# TJMakes_Relay.net
KiCad netlist of a schematic drawn in EasyEDA Pro
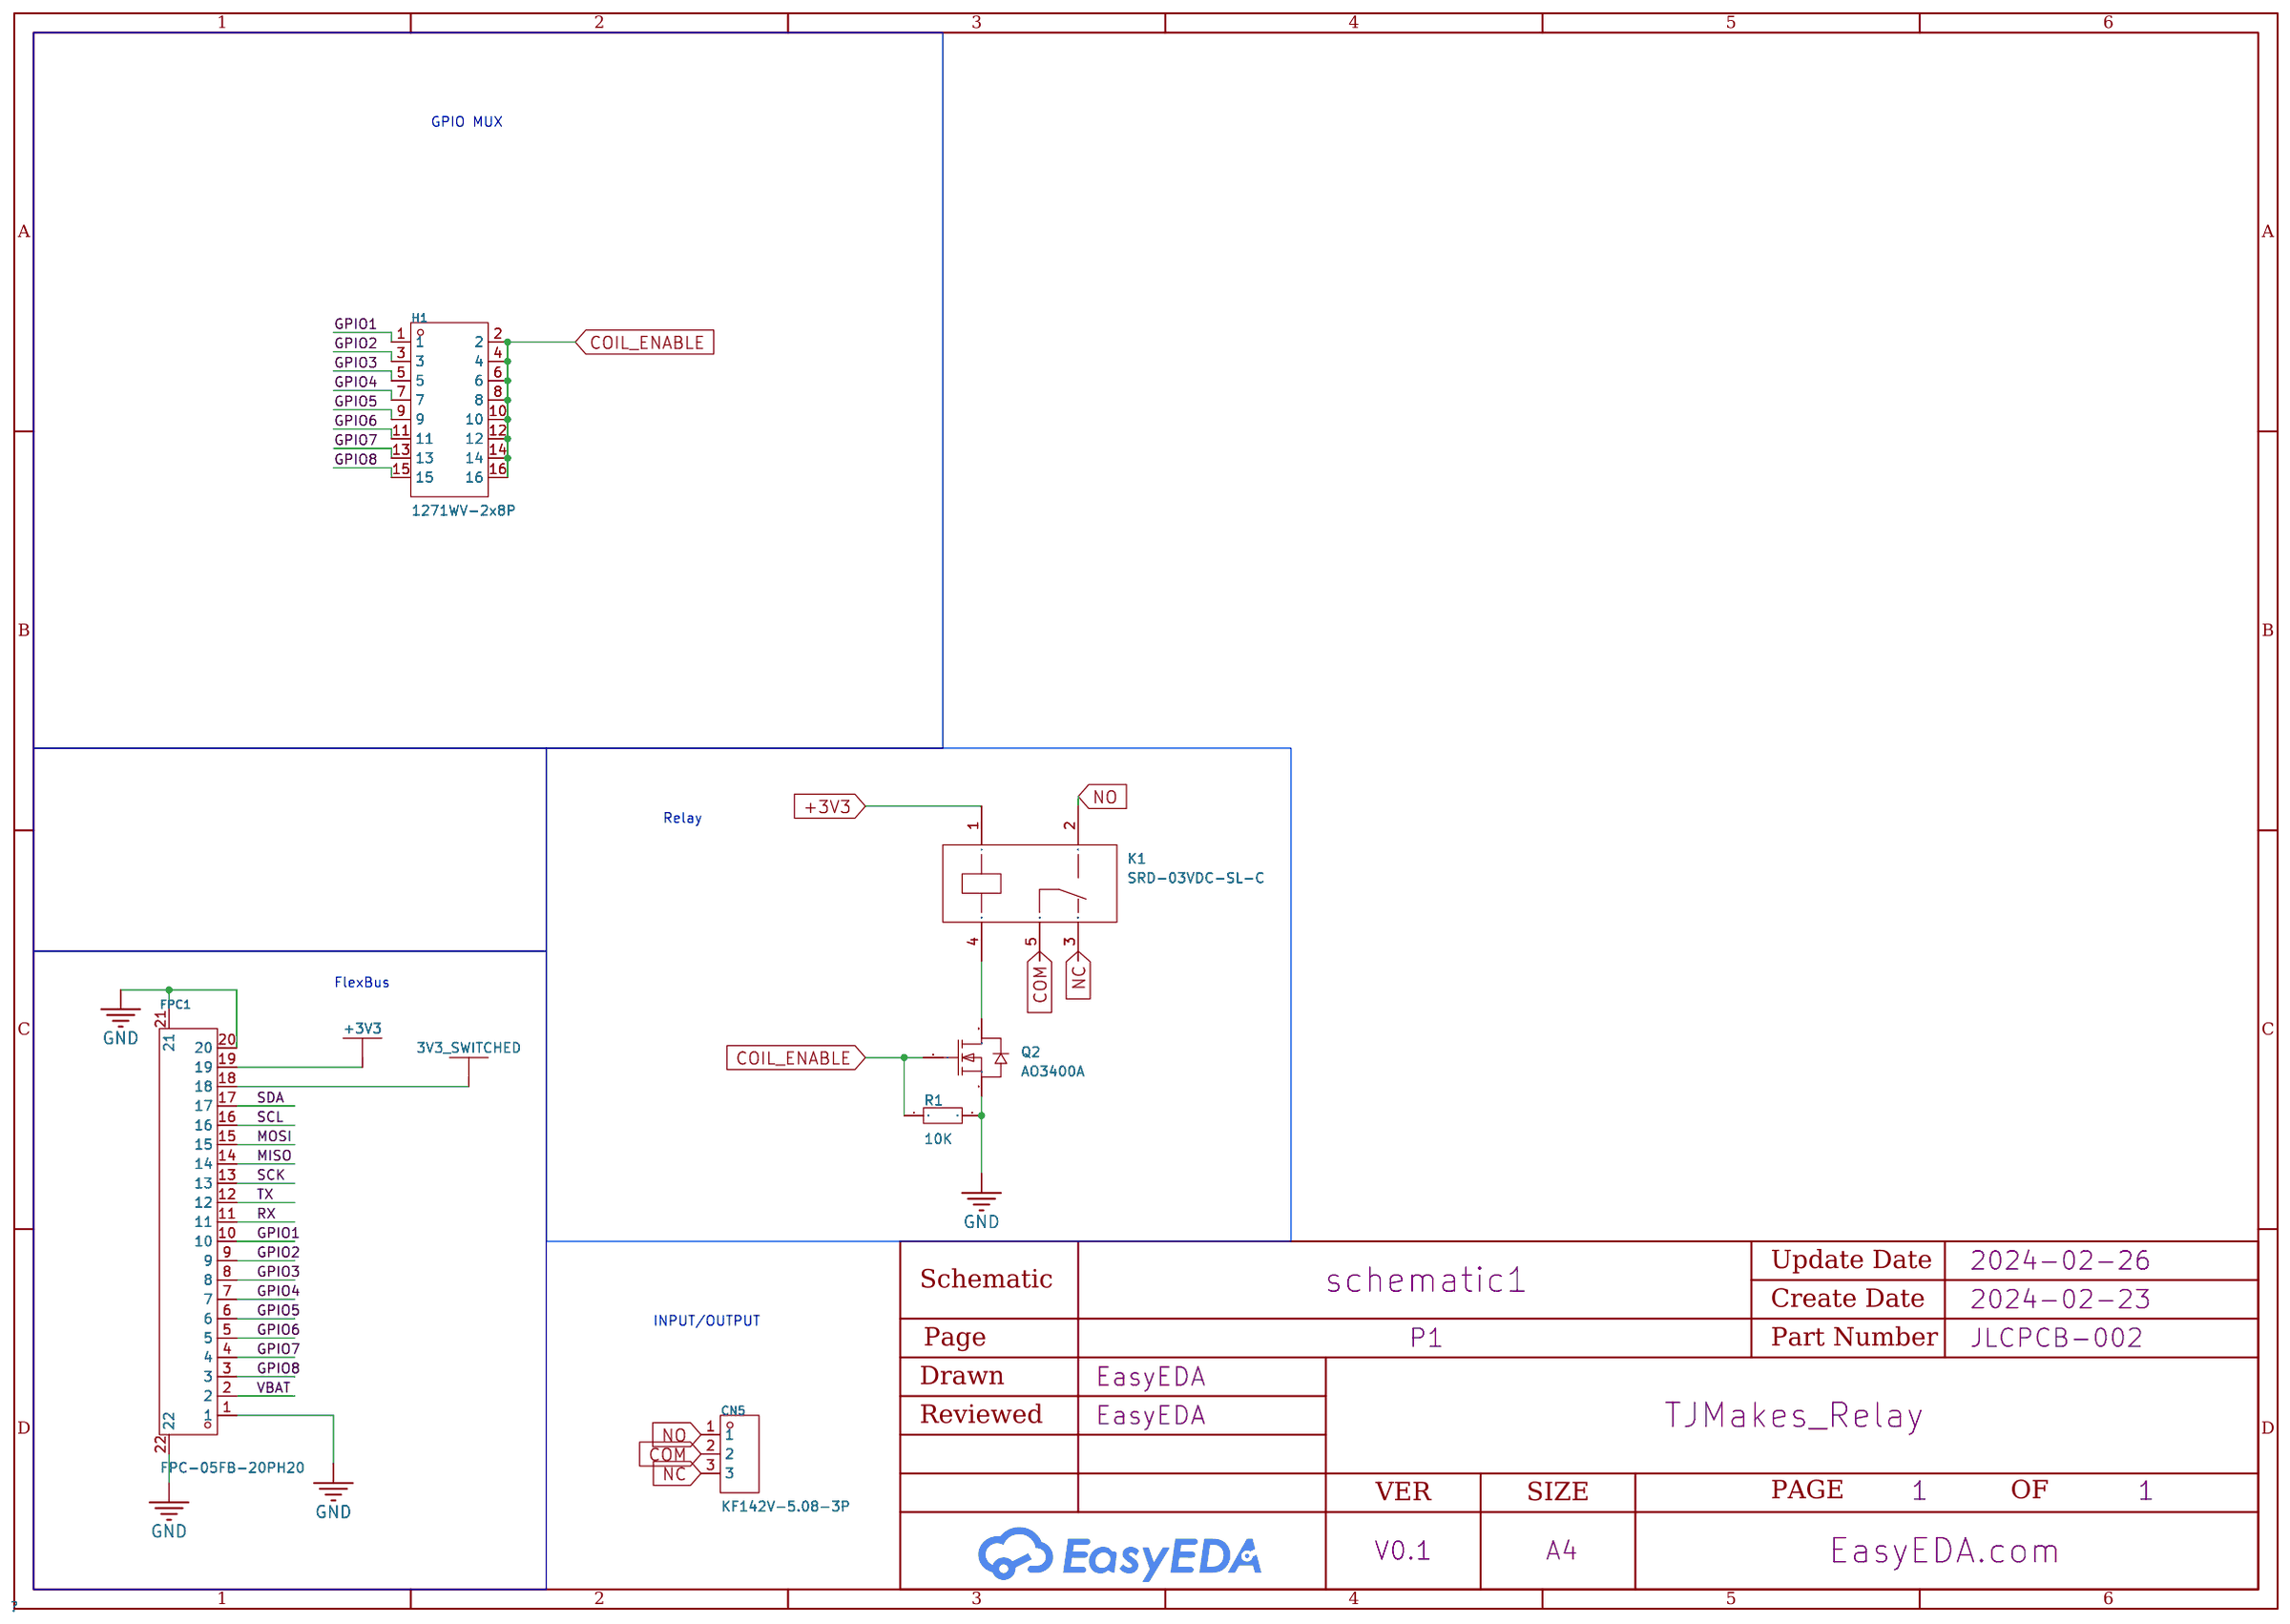
[diagram p0: schematic sheet]

(export (version "E")
  (design (tool "Eeschema 10.0.6"))
  (components
    (comp (ref "CN5")
      (value "KF142V-5.08-3P")
      (footprint "easyedapro:CONN-TH_3P-P5.08_KF142V-5.08-3P")
      (fields (field (name "Manufacturer") "KEFA(科发)"))
      (libsource (lib "easyedapro") (part "KF142V-5.08-3P"))
    )
    (comp (ref "FPC1")
      (value "FPC-05FB-20PH20")
      (footprint "easyedapro:FPC-SMD_20P-P0.50_FPC-05FB-20PH20")
      (fields (field (name "Manufacturer") "XUNPU(讯普)"))
      (libsource (lib "easyedapro") (part "FPC-05FB-20PH20"))
    )
    (comp (ref "H1")
      (value "1271WV-2x8P")
      (footprint "easyedapro:HDR-TH_16P-P1.27-V-M-R2-C8-S1.27")
      (fields (field (name "Manufacturer") "kinghelm(金航标)"))
      (libsource (lib "easyedapro") (part "KH-1.27PH180-2X8P-L7.2"))
    )
    (comp (ref "K1")
      (value "SRD-03VDC-SL-C")
      (footprint "easyedapro:RELAY-TH_SRD-XXVDC-XL-C")
      (fields (field (name "Manufacturer") "松乐"))
      (libsource (lib "easyedapro") (part "SRD-03VDC-SL-C"))
    )
    (comp (ref "Q2")
      (value "AO3400A")
      (footprint "easyedapro:SOT-23-3_L2.9-W1.6-P1.90-LS2.8-BR")
      (fields (field (name "Manufacturer") "AOS"))
      (libsource (lib "easyedapro") (part "AO3400A"))
    )
    (comp (ref "R1") (value "10K") (footprint "easyedapro:R0603") (libsource (lib "easyedapro") (part "Res")))
  )
  (nets
    (net (code "1") (name "+3V3") (class "Default")
      (node (ref "FPC1") (pin "19") (pinfunction "19_19") (pintype "input"))
      (node (ref "K1") (pin "1") (pinfunction "1_1") (pintype "unspecified"))
    )
    (net (code "2") (name "/GPIO1") (class "Default")
      (node (ref "FPC1") (pin "10") (pinfunction "10_10") (pintype "input"))
      (node (ref "H1") (pin "1") (pinfunction "1_1") (pintype "input"))
    )
    (net (code "3") (name "/GPIO2") (class "Default")
      (node (ref "FPC1") (pin "9") (pinfunction "9_9") (pintype "input"))
      (node (ref "H1") (pin "3") (pinfunction "3_3") (pintype "input"))
    )
    (net (code "4") (name "/GPIO3") (class "Default")
      (node (ref "FPC1") (pin "8") (pinfunction "8_8") (pintype "input"))
      (node (ref "H1") (pin "5") (pinfunction "5_5") (pintype "input"))
    )
    (net (code "5") (name "/GPIO4") (class "Default")
      (node (ref "FPC1") (pin "7") (pinfunction "7_7") (pintype "input"))
      (node (ref "H1") (pin "7") (pinfunction "7_7") (pintype "input"))
    )
    (net (code "6") (name "/GPIO5") (class "Default")
      (node (ref "FPC1") (pin "6") (pinfunction "6_6") (pintype "input"))
      (node (ref "H1") (pin "9") (pinfunction "9_9") (pintype "input"))
    )
    (net (code "7") (name "/GPIO6") (class "Default")
      (node (ref "FPC1") (pin "5") (pinfunction "5_5") (pintype "input"))
      (node (ref "H1") (pin "11") (pinfunction "11_11") (pintype "input"))
    )
    (net (code "8") (name "/GPIO7") (class "Default")
      (node (ref "FPC1") (pin "4") (pinfunction "4_4") (pintype "input"))
      (node (ref "H1") (pin "13") (pinfunction "13_13") (pintype "input"))
    )
    (net (code "9") (name "/GPIO8") (class "Default")
      (node (ref "FPC1") (pin "3") (pinfunction "3_3") (pintype "input"))
      (node (ref "H1") (pin "15") (pinfunction "15_15") (pintype "input"))
    )
    (net (code "10") (name "/MISO") (class "Default")
      (node (ref "FPC1") (pin "14") (pinfunction "14_14") (pintype "input"))
    )
    (net (code "11") (name "/MOSI") (class "Default")
      (node (ref "FPC1") (pin "15") (pinfunction "15_15") (pintype "input"))
    )
    (net (code "12") (name "/RX") (class "Default")
      (node (ref "FPC1") (pin "11") (pinfunction "11_11") (pintype "input"))
    )
    (net (code "13") (name "/SCK") (class "Default")
      (node (ref "FPC1") (pin "13") (pinfunction "13_13") (pintype "input"))
    )
    (net (code "14") (name "/SCL") (class "Default")
      (node (ref "FPC1") (pin "16") (pinfunction "16_16") (pintype "input"))
    )
    (net (code "15") (name "/SDA") (class "Default")
      (node (ref "FPC1") (pin "17") (pinfunction "17_17") (pintype "input"))
    )
    (net (code "16") (name "/TX") (class "Default")
      (node (ref "FPC1") (pin "12") (pinfunction "12_12") (pintype "input"))
    )
    (net (code "17") (name "/VBAT") (class "Default")
      (node (ref "FPC1") (pin "2") (pinfunction "2_2") (pintype "input"))
    )
    (net (code "18") (name "3V3_SWITCHED") (class "Default")
      (node (ref "FPC1") (pin "18") (pinfunction "18_18") (pintype "input"))
    )
    (net (code "19") (name "COIL_ENABLE") (class "Default")
      (node (ref "H1") (pin "10") (pinfunction "10_10") (pintype "input"))
      (node (ref "H1") (pin "12") (pinfunction "12_12") (pintype "input"))
      (node (ref "H1") (pin "14") (pinfunction "14_14") (pintype "input"))
      (node (ref "H1") (pin "16") (pinfunction "16_16") (pintype "input"))
      (node (ref "H1") (pin "2") (pinfunction "2_2") (pintype "input"))
      (node (ref "H1") (pin "4") (pinfunction "4_4") (pintype "input"))
      (node (ref "H1") (pin "6") (pinfunction "6_6") (pintype "input"))
      (node (ref "H1") (pin "8") (pinfunction "8_8") (pintype "input"))
      (node (ref "Q2") (pin "1") (pinfunction "G_1") (pintype "input"))
      (node (ref "R1") (pin "1") (pinfunction "1_1") (pintype "input"))
    )
    (net (code "20") (name "COM") (class "Default")
      (node (ref "CN5") (pin "2") (pinfunction "2_2") (pintype "input"))
      (node (ref "K1") (pin "5") (pinfunction "5_5") (pintype "unspecified"))
    )
    (net (code "21") (name "GND") (class "Default")
      (node (ref "FPC1") (pin "1") (pinfunction "1_1") (pintype "input"))
      (node (ref "FPC1") (pin "20") (pinfunction "20_20") (pintype "input"))
      (node (ref "FPC1") (pin "21") (pinfunction "21_21") (pintype "input"))
      (node (ref "FPC1") (pin "22") (pinfunction "22_22") (pintype "input"))
      (node (ref "Q2") (pin "2") (pinfunction "S_2") (pintype "input"))
      (node (ref "R1") (pin "2") (pinfunction "2_2") (pintype "input"))
    )
    (net (code "22") (name "NC") (class "Default")
      (node (ref "CN5") (pin "3") (pinfunction "3_3") (pintype "input"))
      (node (ref "K1") (pin "3") (pinfunction "3_3") (pintype "unspecified"))
    )
    (net (code "23") (name "NO") (class "Default")
      (node (ref "CN5") (pin "1") (pinfunction "1_1") (pintype "input"))
      (node (ref "K1") (pin "2") (pinfunction "2_2") (pintype "unspecified"))
    )
    (net (code "24") (name "Net-(Q2-D)") (class "Default")
      (node (ref "K1") (pin "4") (pinfunction "4_4") (pintype "unspecified"))
      (node (ref "Q2") (pin "3") (pinfunction "D_3") (pintype "input"))
    )
  )
)
